# schematic.net
KiCad netlist of a schematic drawn in EasyEDA
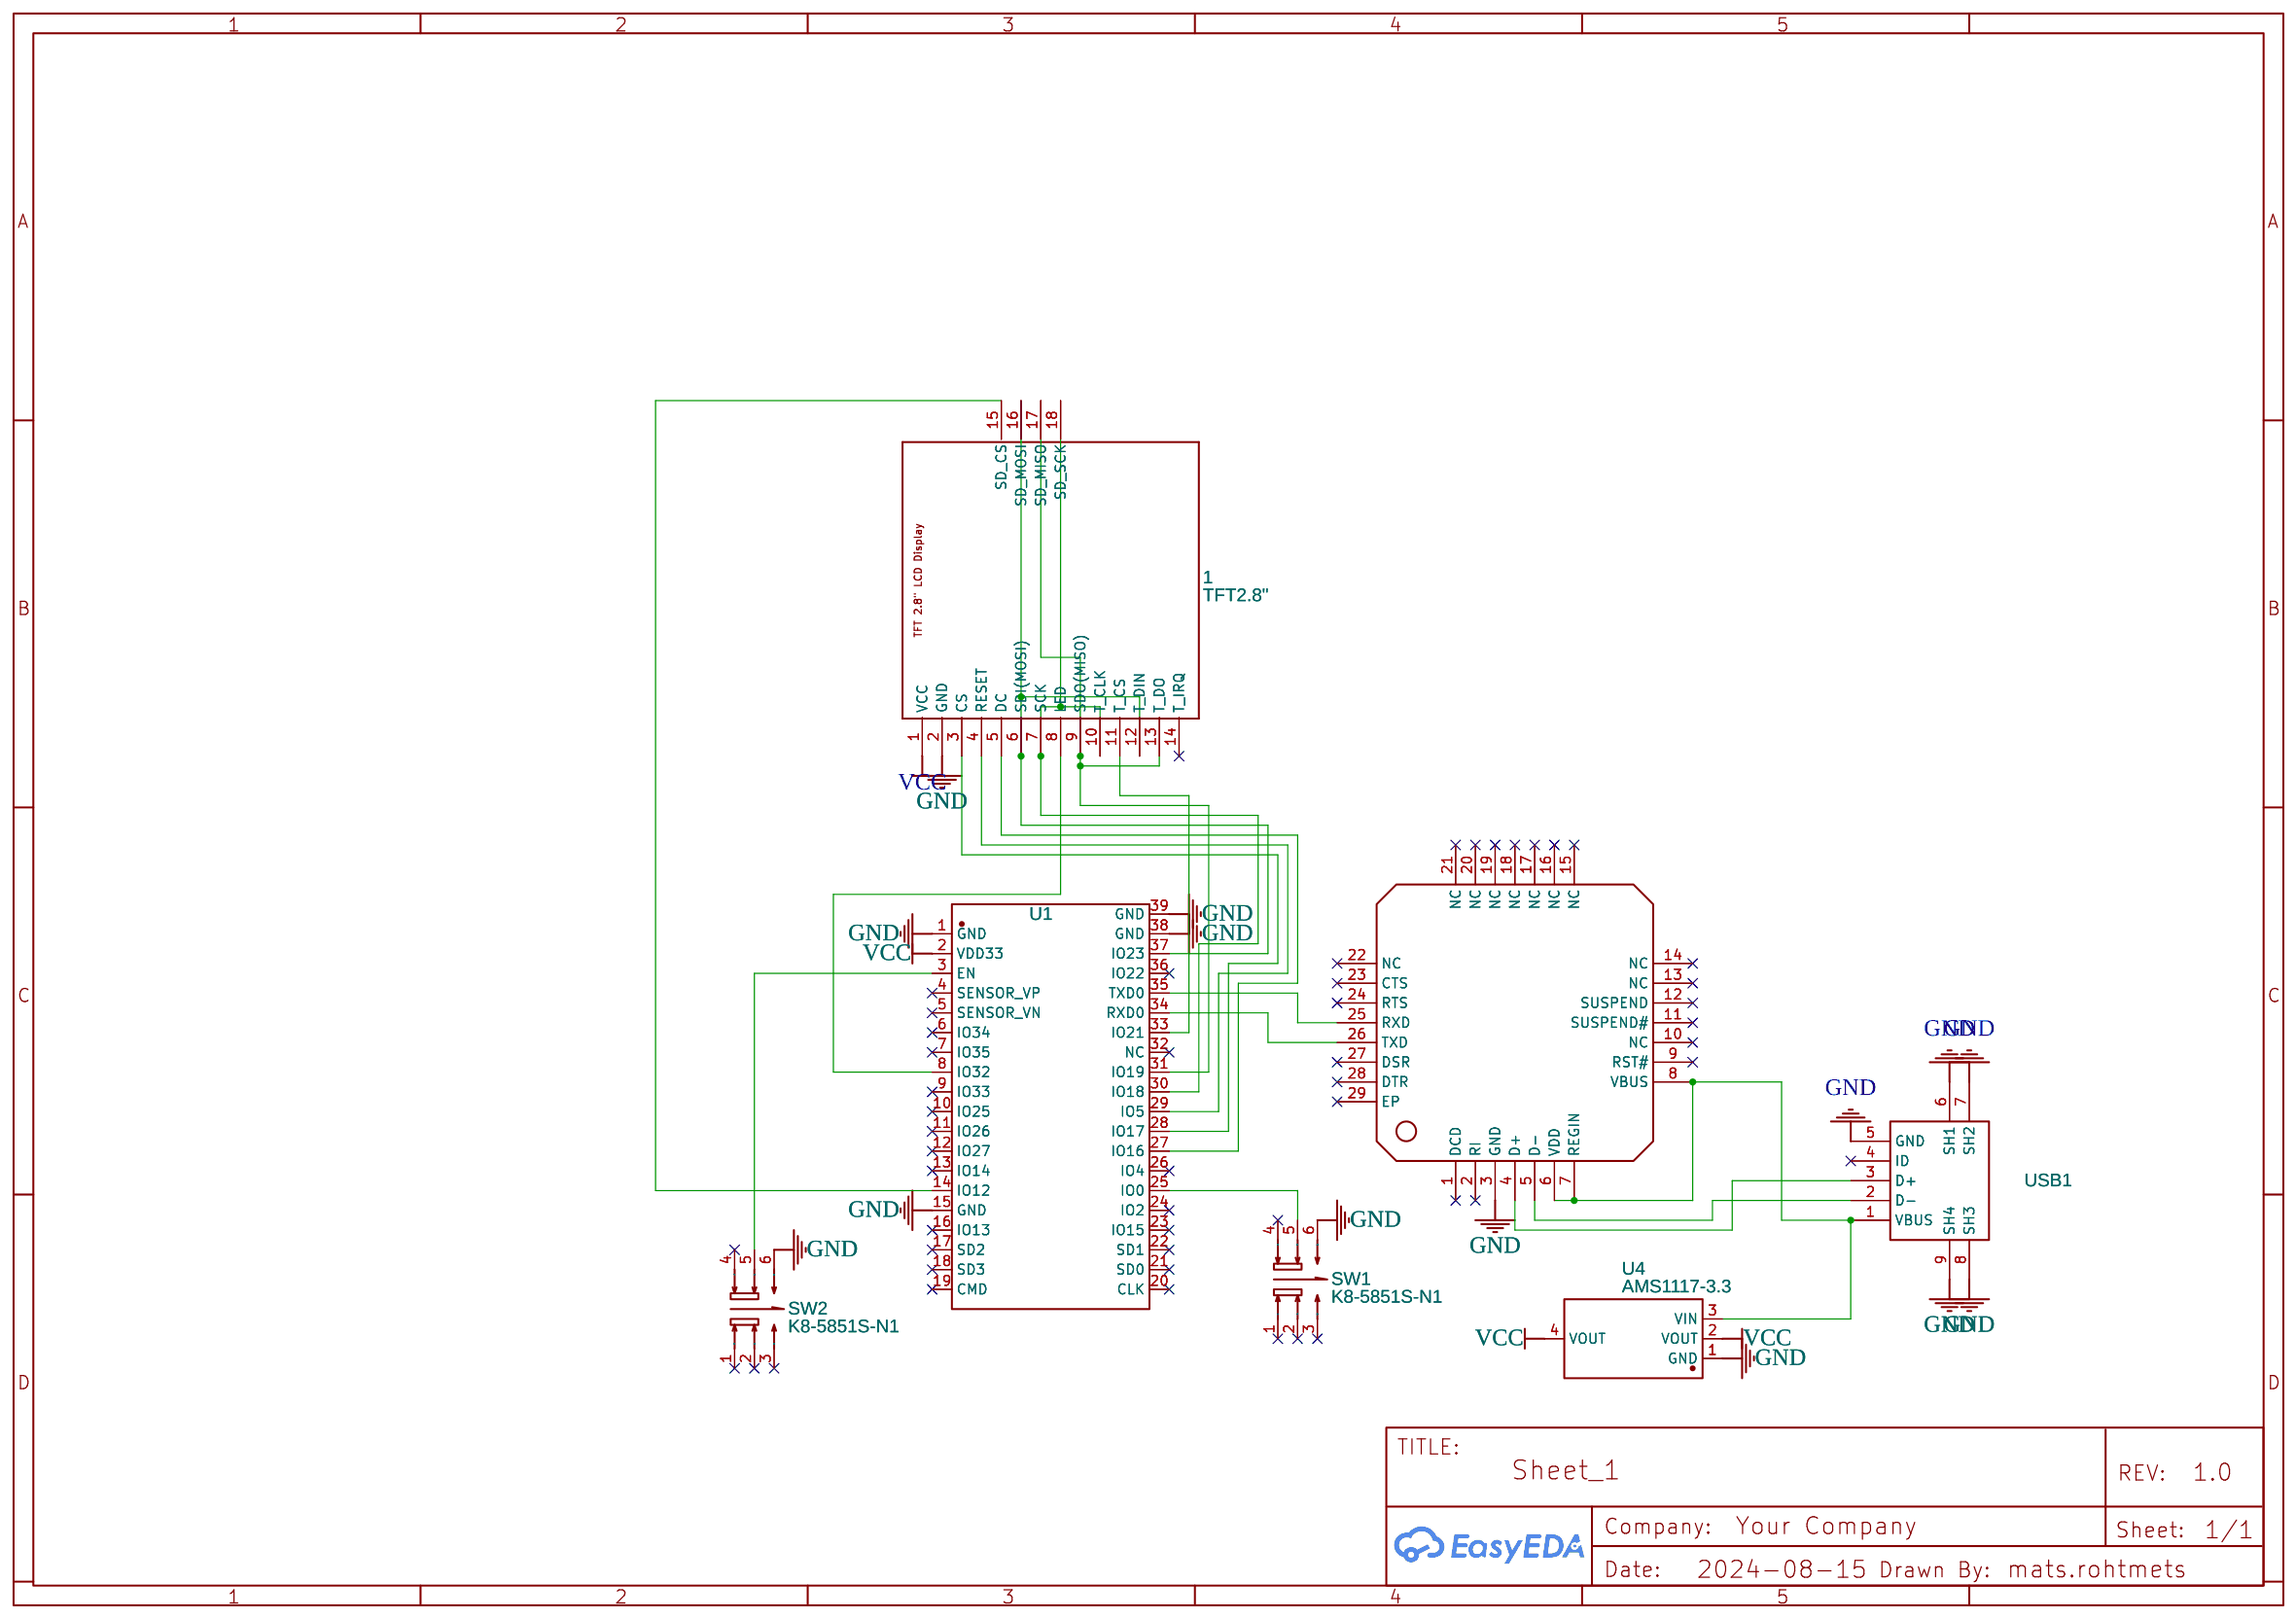
[diagram p0: schematic sheet]

(export (version "E")
  (design (tool "Eeschema 10.0.6"))
  (components
    (comp (ref "1") (value "TFT2.8\"") (libsource (lib "") (part "TFT2.8{dblquote}")))
    (comp (ref "SW1")
      (value "K8-5851S-N1")
      (fields (field (name "Manufacturer") "韩国韩荣"))
      (libsource (lib "") (part "K8-5851S-N1"))
    )
    (comp (ref "SW2")
      (value "K8-5851S-N1")
      (fields (field (name "Manufacturer") "韩国韩荣"))
      (libsource (lib "") (part "K8-5851S-N1"))
    )
    (comp (ref "U1")
      (value "ESP32-WROOM-32U-H4")
      (fields (field (name "Manufacturer") "ESPRESSIF(乐鑫)"))
      (libsource (lib "") (part "ESP32-WROOM-32U-H4"))
    )
    (comp (ref "U3")
      (value "CP2102-GMR")
      (fields (field (name "Manufacturer") "SKYWORKS/SILICON LABS(芯科)"))
      (libsource (lib "") (part "CP2102-GMR"))
    )
    (comp (ref "U4")
      (value "AMS1117-3.3")
      (fields (field (name "Manufacturer") "AMS"))
      (libsource (lib "") (part "AMS1117-3.3"))
    )
    (comp (ref "USB1")
      (value "MICROXNJ")
      (fields (field (name "Manufacturer Part") "MicroXNJ") (field (name "Manufacturer") "SHOU HAN(首韩)"))
      (libsource (lib "") (part "MICROXNJ"))
    )
  )
  (nets
    (net (code "1") (name "GND") (class "Default")
      (node (ref "1") (pin "2") (pinfunction "GND_2") (pintype "bidirectional"))
      (node (ref "SW1") (pin "6") (pinfunction "6_6") (pintype "unspecified"))
      (node (ref "SW2") (pin "6") (pinfunction "6_6") (pintype "unspecified"))
      (node (ref "U1") (pin "1") (pinfunction "GND_1") (pintype "unspecified"))
      (node (ref "U1") (pin "15") (pinfunction "GND_15") (pintype "unspecified"))
      (node (ref "U1") (pin "38") (pinfunction "GND_38") (pintype "unspecified"))
      (node (ref "U1") (pin "39") (pinfunction "GND_39") (pintype "unspecified"))
      (node (ref "U3") (pin "3") (pinfunction "GND_3") (pintype "unspecified"))
      (node (ref "U4") (pin "1") (pinfunction "GND_1") (pintype "unspecified"))
      (node (ref "USB1") (pin "5") (pinfunction "GND_5") (pintype "unspecified"))
      (node (ref "USB1") (pin "6") (pinfunction "SH1_6") (pintype "unspecified"))
      (node (ref "USB1") (pin "7") (pinfunction "SH2_7") (pintype "unspecified"))
      (node (ref "USB1") (pin "8") (pinfunction "SH3_8") (pintype "unspecified"))
      (node (ref "USB1") (pin "9") (pinfunction "SH4_9") (pintype "unspecified"))
    )
    (net (code "2") (name "Net-(1-CS)") (class "Default")
      (node (ref "1") (pin "3") (pinfunction "CS_3") (pintype "bidirectional"))
      (node (ref "U1") (pin "28") (pinfunction "IO17_28") (pintype "unspecified"))
    )
    (net (code "3") (name "Net-(1-DC)") (class "Default")
      (node (ref "1") (pin "5") (pinfunction "DC_5") (pintype "bidirectional"))
      (node (ref "U1") (pin "27") (pinfunction "IO16_27") (pintype "unspecified"))
    )
    (net (code "4") (name "Net-(1-LED)") (class "Default")
      (node (ref "1") (pin "8") (pinfunction "LED_8") (pintype "bidirectional"))
      (node (ref "U1") (pin "8") (pinfunction "IO32_8") (pintype "unspecified"))
    )
    (net (code "5") (name "Net-(1-RESET)") (class "Default")
      (node (ref "1") (pin "4") (pinfunction "RESET_4") (pintype "bidirectional"))
      (node (ref "U1") (pin "29") (pinfunction "IO5_29") (pintype "unspecified"))
    )
    (net (code "6") (name "Net-(1-SCK)") (class "Default")
      (node (ref "1") (pin "10") (pinfunction "T_CLK_10") (pintype "bidirectional"))
      (node (ref "1") (pin "18") (pinfunction "SD_SCK_18") (pintype "bidirectional"))
      (node (ref "1") (pin "7") (pinfunction "SCK_7") (pintype "bidirectional"))
      (node (ref "U1") (pin "30") (pinfunction "IO18_30") (pintype "unspecified"))
    )
    (net (code "7") (name "Net-(1-SDI(MOSI))") (class "Default")
      (node (ref "1") (pin "12") (pinfunction "T_DIN_12") (pintype "bidirectional"))
      (node (ref "1") (pin "16") (pinfunction "SD_MOSI_16") (pintype "bidirectional"))
      (node (ref "1") (pin "6") (pinfunction "SDI(MOSI)_6") (pintype "bidirectional"))
      (node (ref "U1") (pin "37") (pinfunction "IO23_37") (pintype "unspecified"))
    )
    (net (code "8") (name "Net-(1-SDO(MISO))") (class "Default")
      (node (ref "1") (pin "13") (pinfunction "T_DO_13") (pintype "bidirectional"))
      (node (ref "1") (pin "17") (pinfunction "SD_MISO_17") (pintype "bidirectional"))
      (node (ref "1") (pin "9") (pinfunction "SDO(MISO)_9") (pintype "bidirectional"))
      (node (ref "U1") (pin "31") (pinfunction "IO19_31") (pintype "unspecified"))
    )
    (net (code "9") (name "Net-(1-SD_CS)") (class "Default")
      (node (ref "1") (pin "15") (pinfunction "SD_CS_15") (pintype "bidirectional"))
      (node (ref "U1") (pin "14") (pinfunction "IO12_14") (pintype "unspecified"))
    )
    (net (code "10") (name "Net-(1-T_CS)") (class "Default")
      (node (ref "1") (pin "11") (pinfunction "T_CS_11") (pintype "bidirectional"))
      (node (ref "U1") (pin "33") (pinfunction "IO21_33") (pintype "unspecified"))
    )
    (net (code "11") (name "Net-(U1-EN)") (class "Default")
      (node (ref "SW2") (pin "5") (pinfunction "5_5") (pintype "unspecified"))
      (node (ref "U1") (pin "3") (pinfunction "EN_3") (pintype "unspecified"))
    )
    (net (code "12") (name "Net-(U1-IO0)") (class "Default")
      (node (ref "SW1") (pin "5") (pinfunction "5_5") (pintype "unspecified"))
      (node (ref "U1") (pin "25") (pinfunction "IO0_25") (pintype "unspecified"))
    )
    (net (code "13") (name "Net-(U1-RXD0)") (class "Default")
      (node (ref "U1") (pin "34") (pinfunction "RXD0_34") (pintype "unspecified"))
      (node (ref "U3") (pin "26") (pinfunction "TXD_26") (pintype "unspecified"))
    )
    (net (code "14") (name "Net-(U1-TXD0)") (class "Default")
      (node (ref "U1") (pin "35") (pinfunction "TXD0_35") (pintype "unspecified"))
      (node (ref "U3") (pin "25") (pinfunction "RXD_25") (pintype "unspecified"))
    )
    (net (code "15") (name "Net-(U3-D+)") (class "Default")
      (node (ref "U3") (pin "4") (pinfunction "D+_4") (pintype "unspecified"))
      (node (ref "USB1") (pin "3") (pinfunction "D+_3") (pintype "unspecified"))
    )
    (net (code "16") (name "Net-(U3-D-)") (class "Default")
      (node (ref "U3") (pin "5") (pinfunction "D-_5") (pintype "unspecified"))
      (node (ref "USB1") (pin "2") (pinfunction "D-_2") (pintype "unspecified"))
    )
    (net (code "17") (name "Net-(U3-REGIN)") (class "Default")
      (node (ref "U3") (pin "6") (pinfunction "VDD_6") (pintype "unspecified"))
      (node (ref "U3") (pin "7") (pinfunction "REGIN_7") (pintype "unspecified"))
      (node (ref "U3") (pin "8") (pinfunction "VBUS_8") (pintype "unspecified"))
      (node (ref "U4") (pin "3") (pinfunction "VIN_3") (pintype "unspecified"))
      (node (ref "USB1") (pin "1") (pinfunction "VBUS_1") (pintype "unspecified"))
    )
    (net (code "18") (name "VCC") (class "Default")
      (node (ref "1") (pin "1") (pinfunction "VCC_1") (pintype "bidirectional"))
      (node (ref "U1") (pin "2") (pinfunction "VDD33_2") (pintype "unspecified"))
      (node (ref "U4") (pin "2") (pinfunction "VOUT_2") (pintype "unspecified"))
      (node (ref "U4") (pin "4") (pinfunction "VOUT_4") (pintype "unspecified"))
    )
    (net (code "19") (name "unconnected-(1-T_IRQ-Pad14)") (class "Default")
      (node (ref "1") (pin "14") (pinfunction "T_IRQ_14") (pintype "bidirectional+no_connect"))
    )
    (net (code "20") (name "unconnected-(SW1-Pad1)") (class "Default")
      (node (ref "SW1") (pin "1") (pinfunction "1_1") (pintype "unspecified+no_connect"))
    )
    (net (code "21") (name "unconnected-(SW1-Pad2)") (class "Default")
      (node (ref "SW1") (pin "2") (pinfunction "2_2") (pintype "unspecified+no_connect"))
    )
    (net (code "22") (name "unconnected-(SW1-Pad3)") (class "Default")
      (node (ref "SW1") (pin "3") (pinfunction "3_3") (pintype "unspecified+no_connect"))
    )
    (net (code "23") (name "unconnected-(SW1-Pad4)") (class "Default")
      (node (ref "SW1") (pin "4") (pinfunction "4_4") (pintype "unspecified+no_connect"))
    )
    (net (code "24") (name "unconnected-(SW2-Pad1)") (class "Default")
      (node (ref "SW2") (pin "1") (pinfunction "1_1") (pintype "unspecified+no_connect"))
    )
    (net (code "25") (name "unconnected-(SW2-Pad2)") (class "Default")
      (node (ref "SW2") (pin "2") (pinfunction "2_2") (pintype "unspecified+no_connect"))
    )
    (net (code "26") (name "unconnected-(SW2-Pad3)") (class "Default")
      (node (ref "SW2") (pin "3") (pinfunction "3_3") (pintype "unspecified+no_connect"))
    )
    (net (code "27") (name "unconnected-(SW2-Pad4)") (class "Default")
      (node (ref "SW2") (pin "4") (pinfunction "4_4") (pintype "unspecified+no_connect"))
    )
    (net (code "28") (name "unconnected-(U1-CLK-Pad20)") (class "Default")
      (node (ref "U1") (pin "20") (pinfunction "CLK_20") (pintype "unspecified+no_connect"))
    )
    (net (code "29") (name "unconnected-(U1-CMD-Pad19)") (class "Default")
      (node (ref "U1") (pin "19") (pinfunction "CMD_19") (pintype "unspecified+no_connect"))
    )
    (net (code "30") (name "unconnected-(U1-IO2-Pad24)") (class "Default")
      (node (ref "U1") (pin "24") (pinfunction "IO2_24") (pintype "unspecified+no_connect"))
    )
    (net (code "31") (name "unconnected-(U1-IO4-Pad26)") (class "Default")
      (node (ref "U1") (pin "26") (pinfunction "IO4_26") (pintype "unspecified+no_connect"))
    )
    (net (code "32") (name "unconnected-(U1-IO13-Pad16)") (class "Default")
      (node (ref "U1") (pin "16") (pinfunction "IO13_16") (pintype "unspecified+no_connect"))
    )
    (net (code "33") (name "unconnected-(U1-IO14-Pad13)") (class "Default")
      (node (ref "U1") (pin "13") (pinfunction "IO14_13") (pintype "unspecified+no_connect"))
    )
    (net (code "34") (name "unconnected-(U1-IO15-Pad23)") (class "Default")
      (node (ref "U1") (pin "23") (pinfunction "IO15_23") (pintype "unspecified+no_connect"))
    )
    (net (code "35") (name "unconnected-(U1-IO22-Pad36)") (class "Default")
      (node (ref "U1") (pin "36") (pinfunction "IO22_36") (pintype "unspecified+no_connect"))
    )
    (net (code "36") (name "unconnected-(U1-IO25-Pad10)") (class "Default")
      (node (ref "U1") (pin "10") (pinfunction "IO25_10") (pintype "unspecified+no_connect"))
    )
    (net (code "37") (name "unconnected-(U1-IO26-Pad11)") (class "Default")
      (node (ref "U1") (pin "11") (pinfunction "IO26_11") (pintype "unspecified+no_connect"))
    )
    (net (code "38") (name "unconnected-(U1-IO27-Pad12)") (class "Default")
      (node (ref "U1") (pin "12") (pinfunction "IO27_12") (pintype "unspecified+no_connect"))
    )
    (net (code "39") (name "unconnected-(U1-IO33-Pad9)") (class "Default")
      (node (ref "U1") (pin "9") (pinfunction "IO33_9") (pintype "unspecified+no_connect"))
    )
    (net (code "40") (name "unconnected-(U1-IO34-Pad6)") (class "Default")
      (node (ref "U1") (pin "6") (pinfunction "IO34_6") (pintype "unspecified+no_connect"))
    )
    (net (code "41") (name "unconnected-(U1-IO35-Pad7)") (class "Default")
      (node (ref "U1") (pin "7") (pinfunction "IO35_7") (pintype "unspecified+no_connect"))
    )
    (net (code "42") (name "unconnected-(U1-NC-Pad32)") (class "Default")
      (node (ref "U1") (pin "32") (pinfunction "NC_32") (pintype "unspecified+no_connect"))
    )
    (net (code "43") (name "unconnected-(U1-SD0-Pad21)") (class "Default")
      (node (ref "U1") (pin "21") (pinfunction "SD0_21") (pintype "unspecified+no_connect"))
    )
    (net (code "44") (name "unconnected-(U1-SD1-Pad22)") (class "Default")
      (node (ref "U1") (pin "22") (pinfunction "SD1_22") (pintype "unspecified+no_connect"))
    )
    (net (code "45") (name "unconnected-(U1-SD2-Pad17)") (class "Default")
      (node (ref "U1") (pin "17") (pinfunction "SD2_17") (pintype "unspecified+no_connect"))
    )
    (net (code "46") (name "unconnected-(U1-SD3-Pad18)") (class "Default")
      (node (ref "U1") (pin "18") (pinfunction "SD3_18") (pintype "unspecified+no_connect"))
    )
    (net (code "47") (name "unconnected-(U1-SENSOR_VN-Pad5)") (class "Default")
      (node (ref "U1") (pin "5") (pinfunction "SENSOR_VN_5") (pintype "unspecified+no_connect"))
    )
    (net (code "48") (name "unconnected-(U1-SENSOR_VP-Pad4)") (class "Default")
      (node (ref "U1") (pin "4") (pinfunction "SENSOR_VP_4") (pintype "unspecified+no_connect"))
    )
    (net (code "49") (name "unconnected-(U3-CTS-Pad23)") (class "Default")
      (node (ref "U3") (pin "23") (pinfunction "CTS_23") (pintype "unspecified+no_connect"))
    )
    (net (code "50") (name "unconnected-(U3-DCD-Pad1)") (class "Default")
      (node (ref "U3") (pin "1") (pinfunction "DCD_1") (pintype "unspecified+no_connect"))
    )
    (net (code "51") (name "unconnected-(U3-DSR-Pad27)") (class "Default")
      (node (ref "U3") (pin "27") (pinfunction "DSR_27") (pintype "unspecified+no_connect"))
    )
    (net (code "52") (name "unconnected-(U3-DTR-Pad28)") (class "Default")
      (node (ref "U3") (pin "28") (pinfunction "DTR_28") (pintype "unspecified+no_connect"))
    )
    (net (code "53") (name "unconnected-(U3-EP-Pad29)") (class "Default")
      (node (ref "U3") (pin "29") (pinfunction "EP_29") (pintype "unspecified+no_connect"))
    )
    (net (code "54") (name "unconnected-(U3-NC-Pad10)") (class "Default")
      (node (ref "U3") (pin "10") (pinfunction "NC_10") (pintype "unspecified+no_connect"))
    )
    (net (code "55") (name "unconnected-(U3-NC-Pad13)") (class "Default")
      (node (ref "U3") (pin "13") (pinfunction "NC_13") (pintype "unspecified+no_connect"))
    )
    (net (code "56") (name "unconnected-(U3-NC-Pad14)") (class "Default")
      (node (ref "U3") (pin "14") (pinfunction "NC_14") (pintype "unspecified+no_connect"))
    )
    (net (code "57") (name "unconnected-(U3-NC-Pad15)") (class "Default")
      (node (ref "U3") (pin "15") (pinfunction "NC_15") (pintype "unspecified+no_connect"))
    )
    (net (code "58") (name "unconnected-(U3-NC-Pad16)") (class "Default")
      (node (ref "U3") (pin "16") (pinfunction "NC_16") (pintype "unspecified+no_connect"))
    )
    (net (code "59") (name "unconnected-(U3-NC-Pad17)") (class "Default")
      (node (ref "U3") (pin "17") (pinfunction "NC_17") (pintype "unspecified+no_connect"))
    )
    (net (code "60") (name "unconnected-(U3-NC-Pad18)") (class "Default")
      (node (ref "U3") (pin "18") (pinfunction "NC_18") (pintype "unspecified+no_connect"))
    )
    (net (code "61") (name "unconnected-(U3-NC-Pad19)") (class "Default")
      (node (ref "U3") (pin "19") (pinfunction "NC_19") (pintype "unspecified+no_connect"))
    )
    (net (code "62") (name "unconnected-(U3-NC-Pad20)") (class "Default")
      (node (ref "U3") (pin "20") (pinfunction "NC_20") (pintype "unspecified+no_connect"))
    )
    (net (code "63") (name "unconnected-(U3-NC-Pad21)") (class "Default")
      (node (ref "U3") (pin "21") (pinfunction "NC_21") (pintype "unspecified+no_connect"))
    )
    (net (code "64") (name "unconnected-(U3-NC-Pad22)") (class "Default")
      (node (ref "U3") (pin "22") (pinfunction "NC_22") (pintype "unspecified+no_connect"))
    )
    (net (code "65") (name "unconnected-(U3-RI-Pad2)") (class "Default")
      (node (ref "U3") (pin "2") (pinfunction "RI_2") (pintype "unspecified+no_connect"))
    )
    (net (code "66") (name "unconnected-(U3-RST#-Pad9)") (class "Default")
      (node (ref "U3") (pin "9") (pinfunction "RST#_9") (pintype "unspecified+no_connect"))
    )
    (net (code "67") (name "unconnected-(U3-RTS-Pad24)") (class "Default")
      (node (ref "U3") (pin "24") (pinfunction "RTS_24") (pintype "unspecified+no_connect"))
    )
    (net (code "68") (name "unconnected-(U3-SUSPEND#-Pad11)") (class "Default")
      (node (ref "U3") (pin "11") (pinfunction "SUSPEND#_11") (pintype "unspecified+no_connect"))
    )
    (net (code "69") (name "unconnected-(U3-SUSPEND-Pad12)") (class "Default")
      (node (ref "U3") (pin "12") (pinfunction "SUSPEND_12") (pintype "unspecified+no_connect"))
    )
    (net (code "70") (name "unconnected-(USB1-ID-Pad4)") (class "Default")
      (node (ref "USB1") (pin "4") (pinfunction "ID_4") (pintype "unspecified+no_connect"))
    )
  )
)
